# S4_MotorDriver.net
KiCad netlist of a schematic drawn in Altium Designer
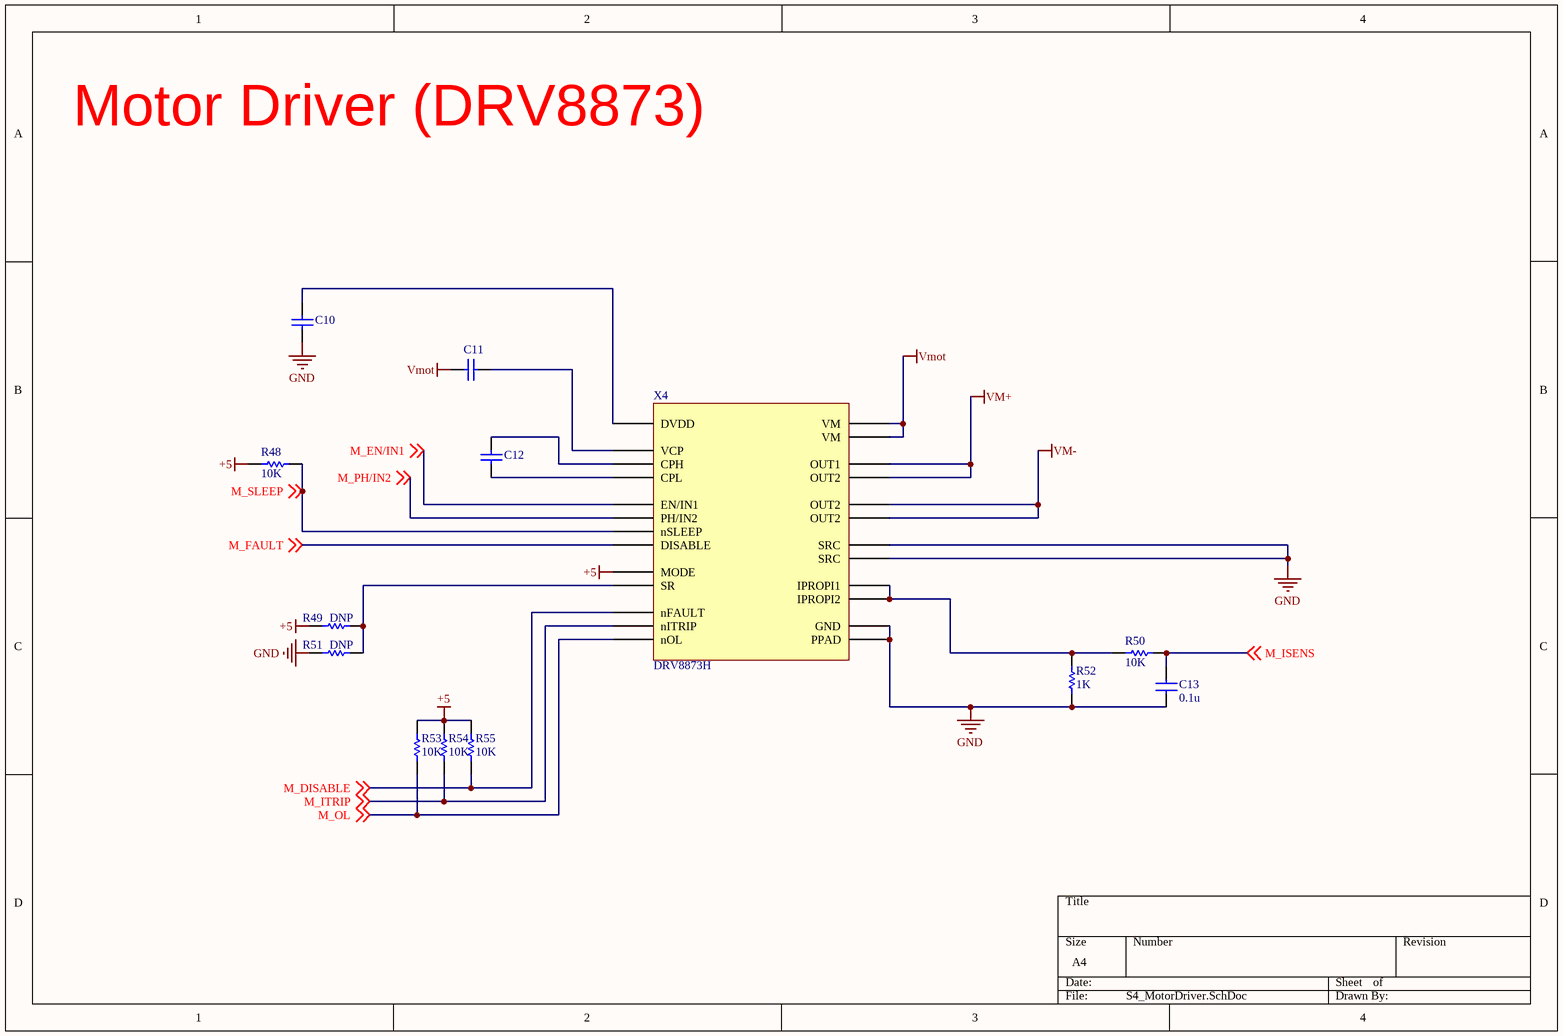
[diagram p0: S4_MotorDriver.SchDoc]

(export (version "E")
  (design (tool "Eeschema 10.0.6"))
  (components
    (comp (ref "C10")
      (value "CAP 1uF 6.3V 1206(3216)")
      (footprint "CAPC1206(3216)130_M")
      (description "CAP 1uF 6.3V ±20% 1206 (3216 Metric) Thickness 1.2mm SMD")
      (fields (field (name "TOLERANCE") "Â±20%"))
      (libsource (lib "Altium Content Vault") (part "CAP"))
    )
    (comp (ref "C11")
      (value "CAP 1uF 25V 1206(3216)")
      (footprint "CAPC1206(3216)130_M")
      (description "CAP 1uF 25V ±10% 1206 (3216 Metric) Thickness 1.3mm SMD")
      (fields (field (name "TOLERANCE") "Â±10%"))
      (libsource (lib "Altium Content Vault") (part "CAP"))
    )
    (comp (ref "C12")
      (value "CAP 47nF 50V 1206(3216)")
      (footprint "CAPC1206(3216)130_L")
      (description "CAP 47nF 50V ±20% 1206 (3216 Metric) Thickness 1.2mm SMD")
      (fields (field (name "TOLERANCE") "Â±20%"))
      (libsource (lib "Altium Content Vault") (part "CAP"))
    )
    (comp (ref "C13")
      (value "0.1u")
      (footprint "Ceramic Cap 5mm")
      (libsource (lib "Res and Cap") (part "Cap"))
    )
    (comp (ref "R48")
      (value "10K")
      (footprint "AXIAL-0.3-3D")
      (description "Resistor")
      (fields (field (name "Comment") "Res1") (field (name "PUBLISHER") "Altium Limited"))
      (libsource (lib "Miscellaneous Devices") (part "Res1"))
    )
    (comp (ref "R49")
      (value "DNP")
      (footprint "AXIAL-0.3-3D")
      (description "Resistor")
      (fields (field (name "Comment") "Res1") (field (name "PUBLISHER") "Altium Limited"))
      (libsource (lib "Miscellaneous Devices") (part "Res1"))
    )
    (comp (ref "R50")
      (value "10K")
      (footprint "AXIAL-0.3-3D")
      (description "Resistor")
      (fields (field (name "Comment") "Res1") (field (name "PUBLISHER") "Altium Limited"))
      (libsource (lib "Miscellaneous Devices") (part "Res1"))
    )
    (comp (ref "R51")
      (value "DNP")
      (footprint "AXIAL-0.3-3D")
      (description "Resistor")
      (fields (field (name "Comment") "Res1") (field (name "PUBLISHER") "Altium Limited"))
      (libsource (lib "Miscellaneous Devices") (part "Res1"))
    )
    (comp (ref "R52")
      (value "1K")
      (footprint "AXIAL-0.3-3D")
      (description "Resistor")
      (fields (field (name "Comment") "Res1") (field (name "PUBLISHER") "Altium Limited"))
      (libsource (lib "Miscellaneous Devices") (part "Res1"))
    )
    (comp (ref "R53")
      (value "10K")
      (footprint "AXIAL-0.3-3D")
      (description "Resistor")
      (fields (field (name "Comment") "Res1") (field (name "PUBLISHER") "Altium Limited"))
      (libsource (lib "Miscellaneous Devices") (part "Res1"))
    )
    (comp (ref "R54")
      (value "10K")
      (footprint "AXIAL-0.3-3D")
      (description "Resistor")
      (fields (field (name "Comment") "Res1") (field (name "PUBLISHER") "Altium Limited"))
      (libsource (lib "Miscellaneous Devices") (part "Res1"))
    )
    (comp (ref "R55")
      (value "10K")
      (footprint "AXIAL-0.3-3D")
      (description "Resistor")
      (fields (field (name "Comment") "Res1") (field (name "PUBLISHER") "Altium Limited"))
      (libsource (lib "Miscellaneous Devices") (part "Res1"))
    )
    (comp (ref "X4") (value "DRV8873H") (footprint "DRV8873") (libsource (lib "Custom") (part "DRV8873")))
  )
  (nets
    (net (code "1") (name "+5") (class "Default")
      (node (ref "R48") (pin "1") (pinfunction "1_1") (pintype "passive"))
      (node (ref "R49") (pin "2") (pinfunction "2_2") (pintype "passive"))
      (node (ref "R53") (pin "2") (pinfunction "2_2") (pintype "passive"))
      (node (ref "R54") (pin "2") (pinfunction "2_2") (pintype "passive"))
      (node (ref "R55") (pin "2") (pinfunction "2_2") (pintype "passive"))
      (node (ref "X4") (pin "3") (pinfunction "MODE_3") (pintype "passive"))
    )
    (net (code "2") (name "GND") (class "Default")
      (node (ref "C10") (pin "1") (pinfunction "1_1") (pintype "passive"))
      (node (ref "C13") (pin "2") (pinfunction "2_2") (pintype "passive"))
      (node (ref "R51") (pin "2") (pinfunction "2_2") (pintype "passive"))
      (node (ref "R52") (pin "2") (pinfunction "2_2") (pintype "passive"))
      (node (ref "X4") (pin "16") (pinfunction "SRC_16") (pintype "passive"))
      (node (ref "X4") (pin "17") (pinfunction "SRC_17") (pintype "passive"))
      (node (ref "X4") (pin "24") (pinfunction "GND_24") (pintype "passive"))
      (node (ref "X4") (pin "25") (pinfunction "PPAD_25") (pintype "passive"))
    )
    (net (code "3") (name "M_DISABLE") (class "Default")
      (node (ref "R55") (pin "1") (pinfunction "1_1") (pintype "passive"))
      (node (ref "X4") (pin "2") (pinfunction "nFAULT_2") (pintype "passive"))
    )
    (net (code "4") (name "M_EN{slash}IN1") (class "Default")
      (node (ref "X4") (pin "7") (pinfunction "EN/IN1_7") (pintype "passive"))
    )
    (net (code "5") (name "M_FAULT") (class "Default")
      (node (ref "X4") (pin "9") (pinfunction "DISABLE_9") (pintype "passive"))
    )
    (net (code "6") (name "M_ISENS") (class "Default")
      (node (ref "C13") (pin "1") (pinfunction "1_1") (pintype "passive"))
      (node (ref "R50") (pin "1") (pinfunction "1_1") (pintype "passive"))
    )
    (net (code "7") (name "M_ITRIP") (class "Default")
      (node (ref "R54") (pin "1") (pinfunction "1_1") (pintype "passive"))
      (node (ref "X4") (pin "5") (pinfunction "nITRIP_5") (pintype "passive"))
    )
    (net (code "8") (name "M_OL") (class "Default")
      (node (ref "R53") (pin "1") (pinfunction "1_1") (pintype "passive"))
      (node (ref "X4") (pin "6") (pinfunction "nOL_6") (pintype "passive"))
    )
    (net (code "9") (name "M_PH{slash}IN2") (class "Default")
      (node (ref "X4") (pin "8") (pinfunction "PH/IN2_8") (pintype "passive"))
    )
    (net (code "10") (name "M_SLEEP") (class "Default")
      (node (ref "R48") (pin "2") (pinfunction "2_2") (pintype "passive"))
      (node (ref "X4") (pin "11") (pinfunction "nSLEEP_11") (pintype "passive"))
    )
    (net (code "11") (name "Net-(X4-CPH)") (class "Default")
      (node (ref "C12") (pin "2") (pinfunction "2_2") (pintype "passive"))
      (node (ref "X4") (pin "22") (pinfunction "CPH_22") (pintype "passive"))
    )
    (net (code "12") (name "Net-(X4-CPL)") (class "Default")
      (node (ref "C12") (pin "1") (pinfunction "1_1") (pintype "passive"))
      (node (ref "X4") (pin "23") (pinfunction "CPL_23") (pintype "passive"))
    )
    (net (code "13") (name "Net-(X4-DVDD)") (class "Default")
      (node (ref "C10") (pin "2") (pinfunction "2_2") (pintype "passive"))
      (node (ref "X4") (pin "1") (pinfunction "DVDD_1") (pintype "passive"))
    )
    (net (code "14") (name "Net-(X4-IPROPI1)") (class "Default")
      (node (ref "R50") (pin "2") (pinfunction "2_2") (pintype "passive"))
      (node (ref "R52") (pin "1") (pinfunction "1_1") (pintype "passive"))
      (node (ref "X4") (pin "10") (pinfunction "IPROPI1_10") (pintype "passive"))
      (node (ref "X4") (pin "12") (pinfunction "IPROPI2_12") (pintype "passive"))
    )
    (net (code "15") (name "Net-(X4-SR)") (class "Default")
      (node (ref "R49") (pin "1") (pinfunction "1_1") (pintype "passive"))
      (node (ref "R51") (pin "1") (pinfunction "1_1") (pintype "passive"))
      (node (ref "X4") (pin "4") (pinfunction "SR_4") (pintype "passive"))
    )
    (net (code "16") (name "Net-(X4-VCP)") (class "Default")
      (node (ref "C11") (pin "2") (pinfunction "2_2") (pintype "passive"))
      (node (ref "X4") (pin "21") (pinfunction "VCP_21") (pintype "passive"))
    )
    (net (code "17") (name "VM+") (class "Default")
      (node (ref "X4") (pin "18") (pinfunction "OUT2_18") (pintype "passive"))
      (node (ref "X4") (pin "19") (pinfunction "OUT1_19") (pintype "passive"))
    )
    (net (code "18") (name "VM-") (class "Default")
      (node (ref "X4") (pin "14") (pinfunction "OUT2_14") (pintype "passive"))
      (node (ref "X4") (pin "15") (pinfunction "OUT2_15") (pintype "passive"))
    )
    (net (code "19") (name "Vmot") (class "Default")
      (node (ref "C11") (pin "1") (pinfunction "1_1") (pintype "passive"))
      (node (ref "X4") (pin "13") (pinfunction "VM_13") (pintype "passive"))
      (node (ref "X4") (pin "20") (pinfunction "VM_20") (pintype "passive"))
    )
  )
)
